# Samtec_Connectors.net
KiCad netlist of a schematic drawn in Altium Designer
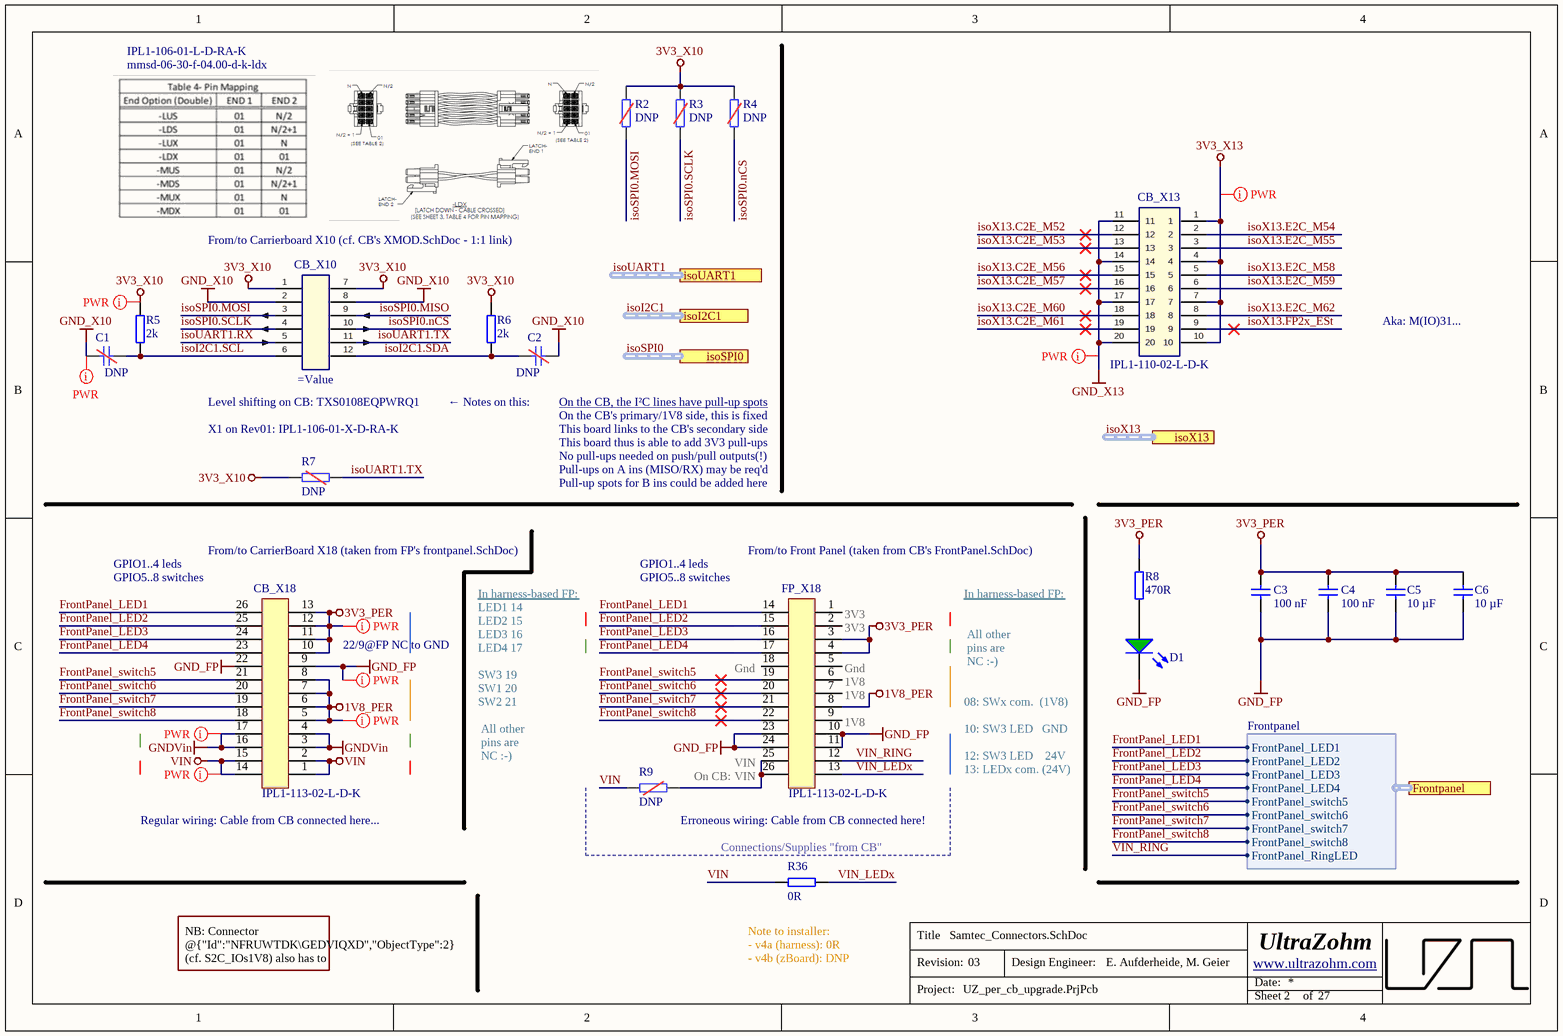
[diagram p0: Samtec_Connectors.SchDoc]

(export (version "E")
  (design (tool "Eeschema 10.0.6"))
  (components
    (comp (ref "C1")
      (value "DNP")
      (footprint "C_0603_TE-DNP")
      (description "Generic capacitor (DNP)")
      (fields
        (field (name "MANUFACTURER PART NUMBER") "UZgen_C_0603_DNP")
        (field (name "MANUFACTURER") "UZgen")
        (field (name "CREATED FROM") "UZgenTool")
      )
      (libsource (lib "user") (part "CAP-NP-DNP"))
    )
    (comp (ref "C2")
      (value "DNP")
      (footprint "C_0603_TE-DNP")
      (description "Generic capacitor (DNP)")
      (fields
        (field (name "MANUFACTURER PART NUMBER") "UZgen_C_0603_DNP")
        (field (name "MANUFACTURER") "UZgen")
        (field (name "CREATED FROM") "UZgenTool")
      )
      (libsource (lib "user") (part "CAP-NP-DNP"))
    )
    (comp (ref "C3")
      (value "100 nF")
      (footprint "C_0603_TE")
      (description "Generic capacitor")
      (fields
        (field (name "TOLERANCE") "10 %")
        (field (name "MANUFACTURER PART NUMBER") "UZgen_C_0603_100nF_50V_X7R")
        (field (name "CREATED FROM") "AGeiger")
      )
      (libsource (lib "user") (part "CAP-NP"))
    )
    (comp (ref "C4")
      (value "100 nF")
      (footprint "C_0603_TE")
      (description "Generic capacitor")
      (fields
        (field (name "TOLERANCE") "10 %")
        (field (name "MANUFACTURER PART NUMBER") "UZgen_C_0603_100nF_50V_X7R")
        (field (name "CREATED FROM") "AGeiger")
      )
      (libsource (lib "user") (part "CAP-NP"))
    )
    (comp (ref "C5")
      (value "10 µF")
      (footprint "C_1206_TE")
      (description "Generic capacitor")
      (fields
        (field (name "TOLERANCE") "10 %")
        (field (name "VOLTAGE") "50V")
        (field (name "CREATED FROM") "MGeier")
      )
      (libsource (lib "user") (part "CAP-NP"))
    )
    (comp (ref "C6")
      (value "10 µF")
      (footprint "C_1206_TE")
      (description "Generic capacitor")
      (fields
        (field (name "TOLERANCE") "10 %")
        (field (name "VOLTAGE") "50V")
        (field (name "CREATED FROM") "MGeier")
      )
      (libsource (lib "user") (part "CAP-NP"))
    )
    (comp (ref "CB_X10")
      (value "~")
      (footprint "IPL1-106-02-L-D-K")
      (description "Headers & Wire Housings .100\" Mini Mate Isolated Power Terminal Header")
      (fields
        (field (name "MANUFACTURER PART NUMBER") "IPL1-106-02-L-D-K")
        (field (name "MANUFACTURER") "SAMTEC")
        (field (name "CREATED FROM") "AGeiger")
      )
      (libsource (lib "user") (part "IPL1-106-XX-X-D-X"))
    )
    (comp (ref "CB_X13")
      (value "IPL1-110-02-L-D-K")
      (footprint "IPL1-110-02-L-D-K")
      (description "2.54 mm Double Row Termin Assembly (SMD)")
      (fields
        (field (name "MANUFACTURER") "SAMTEC")
        (field (name "LCSC PART NUMBER") "C7544188")
        (field (name "CREATED FROM") "MGremer")
      )
      (libsource (lib "user") (part "IPL1-110-XX-X-D-X"))
    )
    (comp (ref "CB_X18")
      (value "IPL1-113-02-L-D-K")
      (footprint "IPL1-113-02-L-D-K")
      (description "2.54 mm Double Row Termin Assembly (SMD)")
      (fields
        (field (name "MANUFACTURER") "SAMTEC")
        (field (name "LCSC PART NUMBER") "C5290052")
        (field (name "CREATED FROM") "MGremer")
      )
      (libsource (lib "user") (part "IPL1-113-XX-X-D-K"))
    )
    (comp (ref "D1")
      (value "LED Green")
      (footprint "WL-SMCW_0603")
      (description "Standard LEDs - SMD 0603 green")
      (fields
        (field (name "MANUFACTURER PART NUMBER") "UZgen_LED_0603_Green")
        (field (name "MANUFACTURER") "UZgen")
        (field (name "CREATED FROM") "UZgenTool")
      )
      (libsource (lib "user") (part "LED_Green"))
    )
    (comp (ref "FP_X18")
      (value "IPL1-113-02-L-D-K")
      (footprint "IPL1-113-02-L-D-K")
      (description "2.54 mm Double Row Termin Assembly (SMD)")
      (fields
        (field (name "MANUFACTURER") "SAMTEC")
        (field (name "LCSC PART NUMBER") "C5290052")
        (field (name "CREATED FROM") "MGremer")
      )
      (libsource (lib "") (part "IPL1-113-XX-X-D-K_1"))
    )
    (comp (ref "R2")
      (value "DNP")
      (footprint "R_0603_TE-DNP")
      (description "Generic resistor (DNP)")
      (fields
        (field (name "MANUFACTURER PART NUMBER") "UZgen_R_0603_DNP")
        (field (name "MANUFACTURER") "UZgen")
        (field (name "CREATED FROM") "UZgenTool")
      )
      (libsource (lib "user") (part "RES-DNP"))
    )
    (comp (ref "R3")
      (value "DNP")
      (footprint "R_0603_TE-DNP")
      (description "Generic resistor (DNP)")
      (fields
        (field (name "MANUFACTURER PART NUMBER") "UZgen_R_0603_DNP")
        (field (name "MANUFACTURER") "UZgen")
        (field (name "CREATED FROM") "UZgenTool")
      )
      (libsource (lib "user") (part "RES-DNP"))
    )
    (comp (ref "R4")
      (value "DNP")
      (footprint "R_0603_TE-DNP")
      (description "Generic resistor (DNP)")
      (fields
        (field (name "MANUFACTURER PART NUMBER") "UZgen_R_0603_DNP")
        (field (name "MANUFACTURER") "UZgen")
        (field (name "CREATED FROM") "UZgenTool")
      )
      (libsource (lib "user") (part "RES-DNP"))
    )
    (comp (ref "R5")
      (value "2k")
      (footprint "R_0603_TE")
      (description "Generic resistor")
      (fields
        (field (name "TOLERANCE") "1 %")
        (field (name "MANUFACTURER PART NUMBER") "UZgen_R_0603_2k")
        (field (name "CREATED FROM") "UZgenTool")
      )
      (libsource (lib "user") (part "RES"))
    )
    (comp (ref "R6")
      (value "2k")
      (footprint "R_0603_TE")
      (description "Generic resistor")
      (fields
        (field (name "TOLERANCE") "1 %")
        (field (name "MANUFACTURER PART NUMBER") "UZgen_R_0603_2k")
        (field (name "CREATED FROM") "UZgenTool")
      )
      (libsource (lib "user") (part "RES"))
    )
    (comp (ref "R7")
      (value "DNP")
      (footprint "R_0603_TE-DNP")
      (description "Generic resistor (DNP)")
      (fields
        (field (name "MANUFACTURER PART NUMBER") "UZgen_R_0603_DNP")
        (field (name "MANUFACTURER") "UZgen")
        (field (name "CREATED FROM") "UZgenTool")
      )
      (libsource (lib "user") (part "RES-DNP"))
    )
    (comp (ref "R8")
      (value "470R")
      (footprint "R_0603_TE")
      (description "Generic resistor")
      (fields
        (field (name "TOLERANCE") "1 %")
        (field (name "MANUFACTURER PART NUMBER") "UZgen_R_0603_470R")
        (field (name "CREATED FROM") "UZgenTool")
      )
      (libsource (lib "user") (part "RES"))
    )
    (comp (ref "R9")
      (value "DNP")
      (footprint "R_0603_TE-DNP")
      (description "Generic resistor (DNP)")
      (fields
        (field (name "MANUFACTURER PART NUMBER") "UZgen_R_0603_DNP")
        (field (name "MANUFACTURER") "UZgen")
        (field (name "CREATED FROM") "UZgenTool")
      )
      (libsource (lib "user") (part "RES-DNP"))
    )
    (comp (ref "R36")
      (value "0R")
      (footprint "R_0603_TE")
      (description "Generic resistor")
      (fields
        (field (name "TOLERANCE") "1 %")
        (field (name "MANUFACTURER PART NUMBER") "UZgen_R_0603_0R")
        (field (name "CREATED FROM") "UZgenTool")
      )
      (libsource (lib "user") (part "RES"))
    )
  )
  (nets
    (net (code "6") (name "/FrontPanel_LED1") (class "Default")
      (node (ref "CB_X18") (pin "26") (pinfunction "26_26") (pintype "passive"))
      (node (ref "FP_X18") (pin "14") (pinfunction "14_14") (pintype "passive"))
    )
    (net (code "7") (name "/FrontPanel_LED2") (class "Default")
      (node (ref "CB_X18") (pin "25") (pinfunction "25_25") (pintype "passive"))
      (node (ref "FP_X18") (pin "15") (pinfunction "15_15") (pintype "passive"))
    )
    (net (code "8") (name "/FrontPanel_LED3") (class "Default")
      (node (ref "CB_X18") (pin "24") (pinfunction "24_24") (pintype "passive"))
      (node (ref "FP_X18") (pin "16") (pinfunction "16_16") (pintype "passive"))
    )
    (net (code "9") (name "/FrontPanel_LED4") (class "Default")
      (node (ref "CB_X18") (pin "23") (pinfunction "23_23") (pintype "passive"))
      (node (ref "FP_X18") (pin "17") (pinfunction "17_17") (pintype "passive"))
    )
    (net (code "10") (name "/FrontPanel_switch5") (class "Default")
      (node (ref "CB_X18") (pin "21") (pinfunction "21_21") (pintype "passive"))
      (node (ref "FP_X18") (pin "19") (pinfunction "19_19") (pintype "passive"))
    )
    (net (code "11") (name "/FrontPanel_switch6") (class "Default")
      (node (ref "CB_X18") (pin "20") (pinfunction "20_20") (pintype "passive"))
      (node (ref "FP_X18") (pin "20") (pinfunction "20_20") (pintype "passive"))
    )
    (net (code "12") (name "/FrontPanel_switch7") (class "Default")
      (node (ref "CB_X18") (pin "19") (pinfunction "19_19") (pintype "passive"))
      (node (ref "FP_X18") (pin "21") (pinfunction "21_21") (pintype "passive"))
    )
    (net (code "13") (name "/FrontPanel_switch8") (class "Default")
      (node (ref "CB_X18") (pin "18") (pinfunction "18_18") (pintype "passive"))
      (node (ref "FP_X18") (pin "22") (pinfunction "22_22") (pintype "passive"))
    )
    (net (code "14") (name "/VIN_LEDx") (class "Default")
      (node (ref "FP_X18") (pin "13") (pinfunction "13_13") (pintype "passive"))
      (node (ref "R36") (pin "2") (pinfunction "2_2") (pintype "passive"))
    )
    (net (code "15") (name "/VIN_RING") (class "Default")
      (node (ref "FP_X18") (pin "12") (pinfunction "12_12") (pintype "passive"))
    )
    (net (code "16") (name "/isoI2C1.SCL") (class "Default")
      (node (ref "C1") (pin "2") (pinfunction "2_2") (pintype "passive"))
      (node (ref "CB_X10") (pin "6") (pinfunction "6_6") (pintype "passive"))
      (node (ref "R5") (pin "1") (pinfunction "1_1") (pintype "passive"))
    )
    (net (code "17") (name "/isoI2C1.SDA") (class "Default")
      (node (ref "C2") (pin "1") (pinfunction "1_1") (pintype "passive"))
      (node (ref "CB_X10") (pin "12") (pinfunction "12_12") (pintype "passive"))
      (node (ref "R6") (pin "1") (pinfunction "1_1") (pintype "passive"))
    )
    (net (code "18") (name "/isoSPI0.MISO") (class "Default")
      (node (ref "CB_X10") (pin "9") (pinfunction "9_9") (pintype "passive"))
    )
    (net (code "19") (name "/isoSPI0.MOSI") (class "Default")
      (node (ref "CB_X10") (pin "3") (pinfunction "3_3") (pintype "passive"))
      (node (ref "R2") (pin "1") (pinfunction "1_1") (pintype "passive"))
    )
    (net (code "20") (name "/isoSPI0.SCLK") (class "Default")
      (node (ref "CB_X10") (pin "4") (pinfunction "4_4") (pintype "passive"))
      (node (ref "R3") (pin "1") (pinfunction "1_1") (pintype "passive"))
    )
    (net (code "21") (name "/isoSPI0.nCS") (class "Default")
      (node (ref "CB_X10") (pin "10") (pinfunction "10_10") (pintype "passive"))
      (node (ref "R4") (pin "1") (pinfunction "1_1") (pintype "passive"))
    )
    (net (code "22") (name "/isoUART1.RX") (class "Default")
      (node (ref "CB_X10") (pin "5") (pinfunction "5_5") (pintype "passive"))
    )
    (net (code "23") (name "/isoUART1.TX") (class "Default")
      (node (ref "CB_X10") (pin "11") (pinfunction "11_11") (pintype "passive"))
      (node (ref "R7") (pin "1") (pinfunction "1_1") (pintype "passive"))
    )
    (net (code "24") (name "/isoX13.C2E_M52") (class "Default")
      (node (ref "CB_X13") (pin "12") (pinfunction "12_12") (pintype "passive"))
    )
    (net (code "25") (name "/isoX13.C2E_M53") (class "Default")
      (node (ref "CB_X13") (pin "13") (pinfunction "13_13") (pintype "passive"))
    )
    (net (code "26") (name "/isoX13.C2E_M56") (class "Default")
      (node (ref "CB_X13") (pin "15") (pinfunction "15_15") (pintype "passive"))
    )
    (net (code "27") (name "/isoX13.C2E_M57") (class "Default")
      (node (ref "CB_X13") (pin "16") (pinfunction "16_16") (pintype "passive"))
    )
    (net (code "28") (name "/isoX13.C2E_M60") (class "Default")
      (node (ref "CB_X13") (pin "18") (pinfunction "18_18") (pintype "passive"))
    )
    (net (code "29") (name "/isoX13.C2E_M61") (class "Default")
      (node (ref "CB_X13") (pin "19") (pinfunction "19_19") (pintype "passive"))
    )
    (net (code "30") (name "/isoX13.E2C_M54") (class "Default")
      (node (ref "CB_X13") (pin "2") (pinfunction "2_2") (pintype "passive"))
    )
    (net (code "31") (name "/isoX13.E2C_M55") (class "Default")
      (node (ref "CB_X13") (pin "3") (pinfunction "3_3") (pintype "passive"))
    )
    (net (code "32") (name "/isoX13.E2C_M58") (class "Default")
      (node (ref "CB_X13") (pin "5") (pinfunction "5_5") (pintype "passive"))
    )
    (net (code "33") (name "/isoX13.E2C_M59") (class "Default")
      (node (ref "CB_X13") (pin "6") (pinfunction "6_6") (pintype "passive"))
    )
    (net (code "34") (name "/isoX13.E2C_M62") (class "Default")
      (node (ref "CB_X13") (pin "8") (pinfunction "8_8") (pintype "passive"))
    )
    (net (code "35") (name "/isoX13.FP2x_ESt") (class "Default")
      (node (ref "CB_X13") (pin "9") (pinfunction "9_9") (pintype "passive"))
    )
    (net (code "41") (name "1V8_PER") (class "Default")
      (node (ref "CB_X18") (pin "5") (pinfunction "5_5") (pintype "passive"))
      (node (ref "CB_X18") (pin "6") (pinfunction "6_6") (pintype "passive"))
      (node (ref "CB_X18") (pin "7") (pinfunction "7_7") (pintype "passive"))
      (node (ref "CB_X18") (pin "8") (pinfunction "8_8") (pintype "passive"))
      (node (ref "FP_X18") (pin "8") (pinfunction "8_8") (pintype "passive"))
    )
    (net (code "42") (name "3V3_PER") (class "Default")
      (node (ref "C3") (pin "1") (pinfunction "1_1") (pintype "passive"))
      (node (ref "C4") (pin "1") (pinfunction "1_1") (pintype "passive"))
      (node (ref "C5") (pin "2") (pinfunction "2_2") (pintype "passive"))
      (node (ref "C6") (pin "2") (pinfunction "2_2") (pintype "passive"))
      (node (ref "CB_X18") (pin "10") (pinfunction "10_10") (pintype "passive"))
      (node (ref "CB_X18") (pin "11") (pinfunction "11_11") (pintype "passive"))
      (node (ref "CB_X18") (pin "12") (pinfunction "12_12") (pintype "passive"))
      (node (ref "CB_X18") (pin "13") (pinfunction "13_13") (pintype "passive"))
      (node (ref "FP_X18") (pin "3") (pinfunction "3_3") (pintype "passive"))
      (node (ref "FP_X18") (pin "4") (pinfunction "4_4") (pintype "passive"))
      (node (ref "R8") (pin "2") (pinfunction "2_2") (pintype "passive"))
    )
    (net (code "43") (name "3V3_X10") (class "Default")
      (node (ref "CB_X10") (pin "1") (pinfunction "1_1") (pintype "passive"))
      (node (ref "CB_X10") (pin "7") (pinfunction "7_7") (pintype "passive"))
      (node (ref "R2") (pin "2") (pinfunction "2_2") (pintype "passive"))
      (node (ref "R3") (pin "2") (pinfunction "2_2") (pintype "passive"))
      (node (ref "R4") (pin "2") (pinfunction "2_2") (pintype "passive"))
      (node (ref "R5") (pin "2") (pinfunction "2_2") (pintype "passive"))
      (node (ref "R6") (pin "2") (pinfunction "2_2") (pintype "passive"))
      (node (ref "R7") (pin "2") (pinfunction "2_2") (pintype "passive"))
    )
    (net (code "44") (name "3V3_X13") (class "Default")
      (node (ref "CB_X13") (pin "1") (pinfunction "1_1") (pintype "passive"))
      (node (ref "CB_X13") (pin "10") (pinfunction "10_10") (pintype "passive"))
      (node (ref "CB_X13") (pin "4") (pinfunction "4_4") (pintype "passive"))
      (node (ref "CB_X13") (pin "7") (pinfunction "7_7") (pintype "passive"))
    )
    (net (code "45") (name "GNDVin") (class "Default")
      (node (ref "CB_X18") (pin "16") (pinfunction "16_16") (pintype "passive"))
      (node (ref "CB_X18") (pin "17") (pinfunction "17_17") (pintype "passive"))
      (node (ref "CB_X18") (pin "3") (pinfunction "3_3") (pintype "passive"))
      (node (ref "CB_X18") (pin "4") (pinfunction "4_4") (pintype "passive"))
    )
    (net (code "46") (name "GND_FP") (class "Default")
      (node (ref "C3") (pin "2") (pinfunction "2_2") (pintype "passive"))
      (node (ref "C4") (pin "2") (pinfunction "2_2") (pintype "passive"))
      (node (ref "C5") (pin "1") (pinfunction "1_1") (pintype "passive"))
      (node (ref "C6") (pin "1") (pinfunction "1_1") (pintype "passive"))
      (node (ref "CB_X18") (pin "22") (pinfunction "22_22") (pintype "passive"))
      (node (ref "CB_X18") (pin "9") (pinfunction "9_9") (pintype "passive"))
      (node (ref "D1") (pin "1") (pinfunction "K_1") (pintype "passive"))
      (node (ref "FP_X18") (pin "10") (pinfunction "10_10") (pintype "passive"))
      (node (ref "FP_X18") (pin "11") (pinfunction "11_11") (pintype "passive"))
      (node (ref "FP_X18") (pin "23") (pinfunction "23_23") (pintype "passive"))
      (node (ref "FP_X18") (pin "24") (pinfunction "24_24") (pintype "passive"))
    )
    (net (code "47") (name "GND_X10") (class "Default")
      (node (ref "C1") (pin "1") (pinfunction "1_1") (pintype "passive"))
      (node (ref "C2") (pin "2") (pinfunction "2_2") (pintype "passive"))
      (node (ref "CB_X10") (pin "2") (pinfunction "2_2") (pintype "passive"))
      (node (ref "CB_X10") (pin "8") (pinfunction "8_8") (pintype "passive"))
    )
    (net (code "48") (name "GND_X13") (class "Default")
      (node (ref "CB_X13") (pin "11") (pinfunction "11_11") (pintype "passive"))
      (node (ref "CB_X13") (pin "14") (pinfunction "14_14") (pintype "passive"))
      (node (ref "CB_X13") (pin "17") (pinfunction "17_17") (pintype "passive"))
      (node (ref "CB_X13") (pin "20") (pinfunction "20_20") (pintype "passive"))
    )
    (net (code "49") (name "Net-(D1-A)") (class "Default")
      (node (ref "D1") (pin "2") (pinfunction "A_2") (pintype "passive"))
      (node (ref "R8") (pin "1") (pinfunction "1_1") (pintype "passive"))
    )
    (net (code "50") (name "Net-(FP_X18-Pad25)") (class "Default")
      (node (ref "FP_X18") (pin "25") (pinfunction "25_25") (pintype "passive"))
      (node (ref "FP_X18") (pin "26") (pinfunction "26_26") (pintype "passive"))
      (node (ref "R9") (pin "2") (pinfunction "2_2") (pintype "passive"))
    )
    (net (code "51") (name "VIN") (class "Default")
      (node (ref "CB_X18") (pin "1") (pinfunction "1_1") (pintype "passive"))
      (node (ref "CB_X18") (pin "14") (pinfunction "14_14") (pintype "passive"))
      (node (ref "CB_X18") (pin "15") (pinfunction "15_15") (pintype "passive"))
      (node (ref "CB_X18") (pin "2") (pinfunction "2_2") (pintype "passive"))
      (node (ref "R36") (pin "1") (pinfunction "1_1") (pintype "passive"))
      (node (ref "R9") (pin "1") (pinfunction "1_1") (pintype "passive"))
    )
    (net (code "52") (name "unconnected-(FP_X18-Pad1)") (class "Default")
      (node (ref "FP_X18") (pin "1") (pinfunction "1_1") (pintype "passive"))
    )
    (net (code "53") (name "unconnected-(FP_X18-Pad2)") (class "Default")
      (node (ref "FP_X18") (pin "2") (pinfunction "2_2") (pintype "passive"))
    )
    (net (code "54") (name "unconnected-(FP_X18-Pad5)") (class "Default")
      (node (ref "FP_X18") (pin "5") (pinfunction "5_5") (pintype "passive"))
    )
    (net (code "55") (name "unconnected-(FP_X18-Pad6)") (class "Default")
      (node (ref "FP_X18") (pin "6") (pinfunction "6_6") (pintype "passive"))
    )
    (net (code "56") (name "unconnected-(FP_X18-Pad7)") (class "Default")
      (node (ref "FP_X18") (pin "7") (pinfunction "7_7") (pintype "passive"))
    )
    (net (code "57") (name "unconnected-(FP_X18-Pad9)") (class "Default")
      (node (ref "FP_X18") (pin "9") (pinfunction "9_9") (pintype "passive"))
    )
    (net (code "58") (name "unconnected-(FP_X18-Pad18)") (class "Default")
      (node (ref "FP_X18") (pin "18") (pinfunction "18_18") (pintype "passive"))
    )
  )
)
